# Step_Motor_Driver.net
KiCad netlist of a schematic drawn in Altium Designer
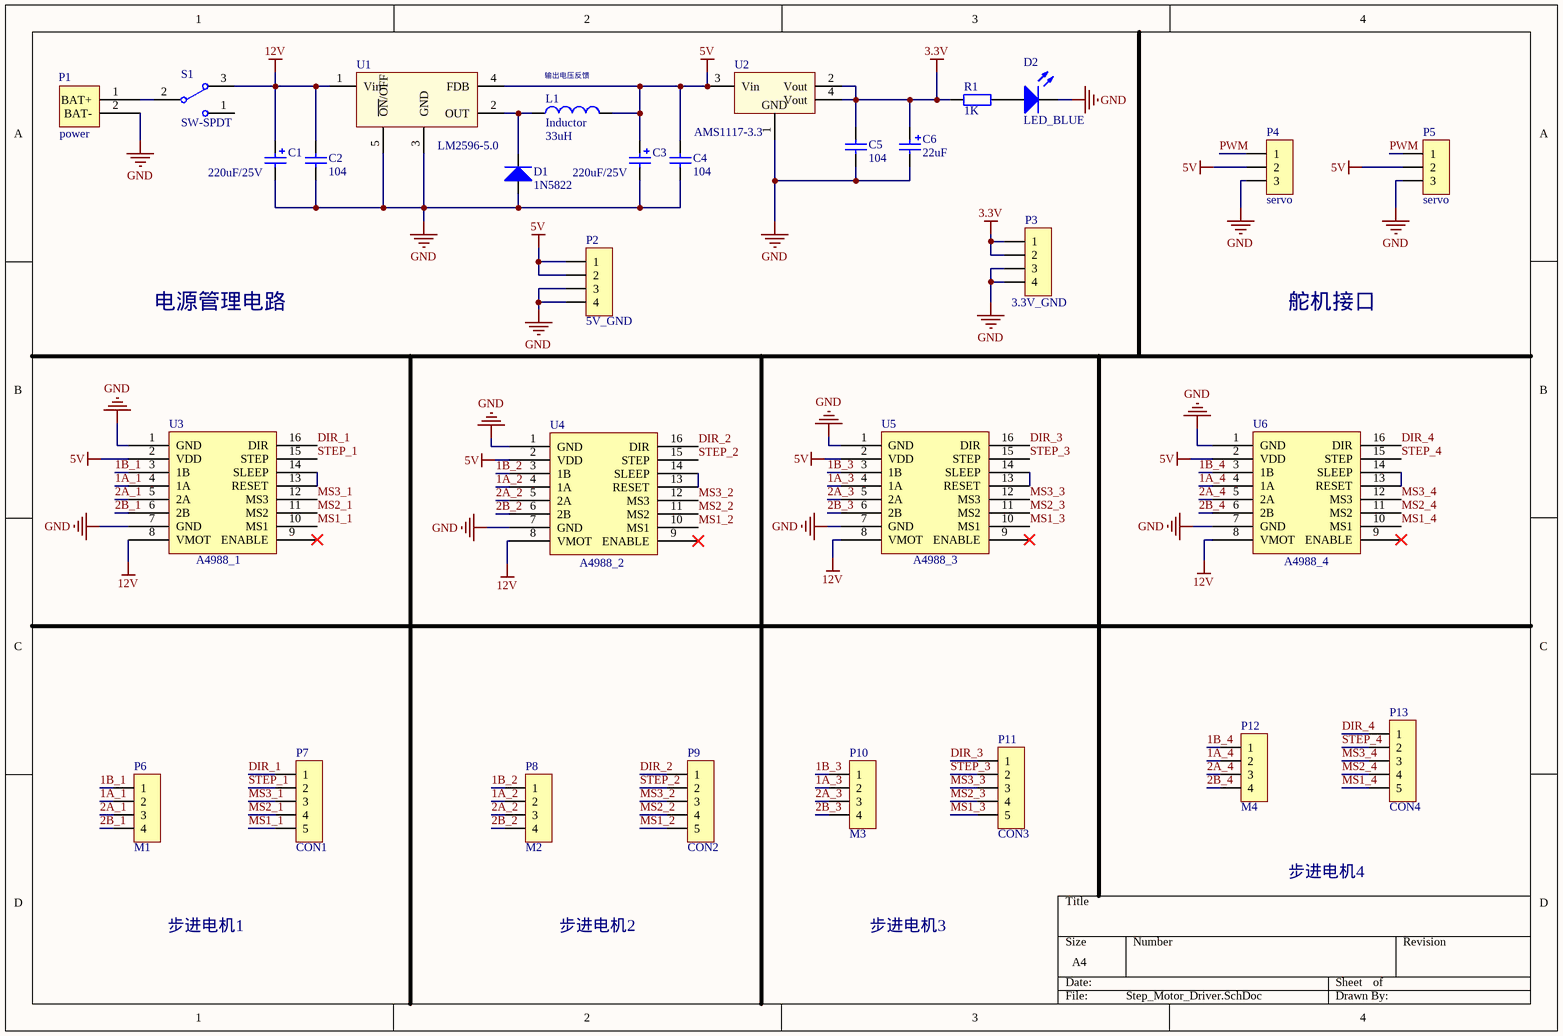
[diagram p0: Step_Motor_Driver.SchDoc]

(export (version "E")
  (design (tool "Eeschema 10.0.6"))
  (components
    (comp (ref "C1")
      (value "220uF/25V")
      (footprint "CAP POL [25V]")
      (description "220uF/35V")
      (libsource (lib "Step_Motor_Driver") (part "Cap Pol [220uF/35V]"))
    )
    (comp (ref "C2")
      (value "Cap")
      (footprint "0805C")
      (fields (field (name "ALTIUM_UNNAMED_1") "104"))
      (libsource (lib "Step_Motor_Driver") (part "Cap_1"))
    )
    (comp (ref "C3")
      (value "220uF/25V")
      (footprint "CAP POL [25V]")
      (description "220uF/35V")
      (libsource (lib "Step_Motor_Driver") (part "Cap Pol [220uF/35V]"))
    )
    (comp (ref "C4")
      (value "Cap")
      (footprint "0805C")
      (fields (field (name "ALTIUM_UNNAMED_1") "104"))
      (libsource (lib "Step_Motor_Driver") (part "Cap_1"))
    )
    (comp (ref "C5")
      (value "Cap")
      (footprint "0805C")
      (fields (field (name "ALTIUM_UNNAMED_1") "104"))
      (libsource (lib "Step_Motor_Driver") (part "Cap_1"))
    )
    (comp (ref "C6")
      (value "Cap Pol(22uF)")
      (footprint "CAP[1210]")
      (fields (field (name "ALTIUM_UNNAMED_1") "22uF"))
      (libsource (lib "Step_Motor_Driver") (part "Cap Pol(22uF)"))
    )
    (comp (ref "D1")
      (value "1N5822")
      (footprint "SS34_3D")
      (description "二极管")
      (libsource (lib "Step_Motor_Driver") (part "1N5819_1"))
    )
    (comp (ref "D2")
      (value "LED_BLUE")
      (footprint "0805LED1")
      (libsource (lib "Step_Motor_Driver") (part "LED_BLUE"))
    )
    (comp (ref "L1")
      (value "Inductor")
      (footprint "Inductor_T10uH")
      (fields (field (name "ALTIUM_UNNAMED_1") "33uH"))
      (libsource (lib "Step_Motor_Driver") (part "Inductor_1"))
    )
    (comp (ref "P1")
      (value "power")
      (footprint "电源端子")
      (description "电源输入")
      (libsource (lib "Step_Motor_Driver") (part "POWER"))
    )
    (comp (ref "P2")
      (value "5V_GND")
      (footprint "HDR2.54-LI-4P")
      (description "4P接插件")
      (fields (field (name "版权归属") "源创客"))
      (libsource (lib "Step_Motor_Driver") (part "Header 4"))
    )
    (comp (ref "P3")
      (value "3.3V_GND")
      (footprint "HDR2.54-LI-4P")
      (description "4P接插件")
      (fields (field (name "版权归属") "源创客"))
      (libsource (lib "Step_Motor_Driver") (part "Header 4"))
    )
    (comp (ref "P4")
      (value "servo")
      (footprint "HDR2.54-LI-3P")
      (description "3P接插件")
      (fields (field (name "版权归属") "源创客"))
      (libsource (lib "Step_Motor_Driver") (part "Header 3"))
    )
    (comp (ref "P5")
      (value "servo")
      (footprint "HDR2.54-LI-3P")
      (description "3P接插件")
      (fields (field (name "版权归属") "源创客"))
      (libsource (lib "Step_Motor_Driver") (part "Header 3"))
    )
    (comp (ref "P6")
      (value "M1")
      (footprint "HDR2.54-LI-4P")
      (description "4P接插件")
      (fields (field (name "版权归属") "源创客"))
      (libsource (lib "Step_Motor_Driver") (part "Header 4"))
    )
    (comp (ref "P7")
      (value "CON1")
      (footprint "HDR2.54-LI-5P")
      (description "5P接插件")
      (fields (field (name "版权归属") "源创客"))
      (libsource (lib "Step_Motor_Driver") (part "Header 5"))
    )
    (comp (ref "P8")
      (value "M2")
      (footprint "HDR2.54-LI-4P")
      (description "4P接插件")
      (fields (field (name "版权归属") "源创客"))
      (libsource (lib "Step_Motor_Driver") (part "Header 4"))
    )
    (comp (ref "P9")
      (value "CON2")
      (footprint "HDR2.54-LI-5P")
      (description "5P接插件")
      (fields (field (name "版权归属") "源创客"))
      (libsource (lib "Step_Motor_Driver") (part "Header 5"))
    )
    (comp (ref "P10")
      (value "M3")
      (footprint "HDR2.54-LI-4P")
      (description "4P接插件")
      (fields (field (name "版权归属") "源创客"))
      (libsource (lib "Step_Motor_Driver") (part "Header 4"))
    )
    (comp (ref "P11")
      (value "CON3")
      (footprint "HDR2.54-LI-5P")
      (description "5P接插件")
      (fields (field (name "版权归属") "源创客"))
      (libsource (lib "Step_Motor_Driver") (part "Header 5"))
    )
    (comp (ref "P12")
      (value "M4")
      (footprint "HDR2.54-LI-4P")
      (description "4P接插件")
      (fields (field (name "版权归属") "源创客"))
      (libsource (lib "Step_Motor_Driver") (part "Header 4"))
    )
    (comp (ref "P13")
      (value "CON4")
      (footprint "HDR2.54-LI-5P")
      (description "5P接插件")
      (fields (field (name "版权归属") "源创客"))
      (libsource (lib "Step_Motor_Driver") (part "Header 5"))
    )
    (comp (ref "R1")
      (value "Res2")
      (footprint "0805R")
      (fields (field (name "ALTIUM_UNNAMED_1") "1K"))
      (libsource (lib "Step_Motor_Driver") (part "Res2"))
    )
    (comp (ref "S1")
      (value "SW-SPDT")
      (footprint "SW-TO3")
      (description "SPDT Subminiature Toggle Switch, Right Angle Mounting, Vertical Actuation")
      (fields (field (name "PUBLISHER") "Altium Limited"))
      (libsource (lib "Step_Motor_Driver") (part "SW-SPDT"))
    )
    (comp (ref "U1")
      (value "LM2596-5.0")
      (footprint "TO-263-5")
      (description "IC")
      (libsource (lib "Step_Motor_Driver") (part "LM2596-5.0"))
    )
    (comp (ref "U2")
      (value "AMS1117-3.3")
      (footprint "SOT-223")
      (libsource (lib "Step_Motor_Driver") (part "AMS1117-3.3"))
    )
    (comp (ref "U3")
      (value "A4988_1")
      (footprint "A4988")
      (description "A4988 Module")
      (libsource (lib "Step_Motor_Driver") (part "A4988"))
    )
    (comp (ref "U4")
      (value "A4988_2")
      (footprint "A4988")
      (description "A4988 Module")
      (libsource (lib "Step_Motor_Driver") (part "A4988"))
    )
    (comp (ref "U5")
      (value "A4988_3")
      (footprint "A4988")
      (description "A4988 Module")
      (libsource (lib "Step_Motor_Driver") (part "A4988"))
    )
    (comp (ref "U6")
      (value "A4988_4")
      (footprint "A4988")
      (description "A4988 Module")
      (libsource (lib "Step_Motor_Driver") (part "A4988"))
    )
  )
  (nets
    (net (code "1") (name "/1A_1") (class "Default")
      (node (ref "P6") (pin "2") (pinfunction "2_2") (pintype "passive"))
      (node (ref "U3") (pin "4") (pinfunction "1A_4") (pintype "passive"))
    )
    (net (code "2") (name "/1A_2") (class "Default")
      (node (ref "P8") (pin "2") (pinfunction "2_2") (pintype "passive"))
      (node (ref "U4") (pin "4") (pinfunction "1A_4") (pintype "passive"))
    )
    (net (code "3") (name "/1A_3") (class "Default")
      (node (ref "P10") (pin "2") (pinfunction "2_2") (pintype "passive"))
      (node (ref "U5") (pin "4") (pinfunction "1A_4") (pintype "passive"))
    )
    (net (code "4") (name "/1A_4") (class "Default")
      (node (ref "P12") (pin "2") (pinfunction "2_2") (pintype "passive"))
      (node (ref "U6") (pin "4") (pinfunction "1A_4") (pintype "passive"))
    )
    (net (code "5") (name "/1B_1") (class "Default")
      (node (ref "P6") (pin "1") (pinfunction "1_1") (pintype "passive"))
      (node (ref "U3") (pin "3") (pinfunction "1B_3") (pintype "passive"))
    )
    (net (code "6") (name "/1B_2") (class "Default")
      (node (ref "P8") (pin "1") (pinfunction "1_1") (pintype "passive"))
      (node (ref "U4") (pin "3") (pinfunction "1B_3") (pintype "passive"))
    )
    (net (code "7") (name "/1B_3") (class "Default")
      (node (ref "P10") (pin "1") (pinfunction "1_1") (pintype "passive"))
      (node (ref "U5") (pin "3") (pinfunction "1B_3") (pintype "passive"))
    )
    (net (code "8") (name "/1B_4") (class "Default")
      (node (ref "P12") (pin "1") (pinfunction "1_1") (pintype "passive"))
      (node (ref "U6") (pin "3") (pinfunction "1B_3") (pintype "passive"))
    )
    (net (code "9") (name "/2A_1") (class "Default")
      (node (ref "P6") (pin "3") (pinfunction "3_3") (pintype "passive"))
      (node (ref "U3") (pin "5") (pinfunction "2A_5") (pintype "passive"))
    )
    (net (code "10") (name "/2A_2") (class "Default")
      (node (ref "P8") (pin "3") (pinfunction "3_3") (pintype "passive"))
      (node (ref "U4") (pin "5") (pinfunction "2A_5") (pintype "passive"))
    )
    (net (code "11") (name "/2A_3") (class "Default")
      (node (ref "P10") (pin "3") (pinfunction "3_3") (pintype "passive"))
      (node (ref "U5") (pin "5") (pinfunction "2A_5") (pintype "passive"))
    )
    (net (code "12") (name "/2A_4") (class "Default")
      (node (ref "P12") (pin "3") (pinfunction "3_3") (pintype "passive"))
      (node (ref "U6") (pin "5") (pinfunction "2A_5") (pintype "passive"))
    )
    (net (code "13") (name "/2B_1") (class "Default")
      (node (ref "P6") (pin "4") (pinfunction "4_4") (pintype "passive"))
      (node (ref "U3") (pin "6") (pinfunction "2B_6") (pintype "passive"))
    )
    (net (code "14") (name "/2B_2") (class "Default")
      (node (ref "P8") (pin "4") (pinfunction "4_4") (pintype "passive"))
      (node (ref "U4") (pin "6") (pinfunction "2B_6") (pintype "passive"))
    )
    (net (code "15") (name "/2B_3") (class "Default")
      (node (ref "P10") (pin "4") (pinfunction "4_4") (pintype "passive"))
      (node (ref "U5") (pin "6") (pinfunction "2B_6") (pintype "passive"))
    )
    (net (code "16") (name "/2B_4") (class "Default")
      (node (ref "P12") (pin "4") (pinfunction "4_4") (pintype "passive"))
      (node (ref "U6") (pin "6") (pinfunction "2B_6") (pintype "passive"))
    )
    (net (code "17") (name "/DIR_1") (class "Default")
      (node (ref "P7") (pin "1") (pinfunction "1_1") (pintype "passive"))
      (node (ref "U3") (pin "16") (pinfunction "DIR_16") (pintype "passive"))
    )
    (net (code "18") (name "/DIR_2") (class "Default")
      (node (ref "P9") (pin "1") (pinfunction "1_1") (pintype "passive"))
      (node (ref "U4") (pin "16") (pinfunction "DIR_16") (pintype "passive"))
    )
    (net (code "19") (name "/DIR_3") (class "Default")
      (node (ref "P11") (pin "1") (pinfunction "1_1") (pintype "passive"))
      (node (ref "U5") (pin "16") (pinfunction "DIR_16") (pintype "passive"))
    )
    (net (code "20") (name "/DIR_4") (class "Default")
      (node (ref "P13") (pin "1") (pinfunction "1_1") (pintype "passive"))
      (node (ref "U6") (pin "16") (pinfunction "DIR_16") (pintype "passive"))
    )
    (net (code "21") (name "/MS1_1") (class "Default")
      (node (ref "P7") (pin "5") (pinfunction "5_5") (pintype "passive"))
      (node (ref "U3") (pin "10") (pinfunction "MS1_10") (pintype "passive"))
    )
    (net (code "22") (name "/MS1_2") (class "Default")
      (node (ref "P9") (pin "5") (pinfunction "5_5") (pintype "passive"))
      (node (ref "U4") (pin "10") (pinfunction "MS1_10") (pintype "passive"))
    )
    (net (code "23") (name "/MS1_3") (class "Default")
      (node (ref "P11") (pin "5") (pinfunction "5_5") (pintype "passive"))
      (node (ref "U5") (pin "10") (pinfunction "MS1_10") (pintype "passive"))
    )
    (net (code "24") (name "/MS1_4") (class "Default")
      (node (ref "P13") (pin "5") (pinfunction "5_5") (pintype "passive"))
      (node (ref "U6") (pin "10") (pinfunction "MS1_10") (pintype "passive"))
    )
    (net (code "25") (name "/MS2_1") (class "Default")
      (node (ref "P7") (pin "4") (pinfunction "4_4") (pintype "passive"))
      (node (ref "U3") (pin "11") (pinfunction "MS2_11") (pintype "passive"))
    )
    (net (code "26") (name "/MS2_2") (class "Default")
      (node (ref "P9") (pin "4") (pinfunction "4_4") (pintype "passive"))
      (node (ref "U4") (pin "11") (pinfunction "MS2_11") (pintype "passive"))
    )
    (net (code "27") (name "/MS2_3") (class "Default")
      (node (ref "P11") (pin "4") (pinfunction "4_4") (pintype "passive"))
      (node (ref "U5") (pin "11") (pinfunction "MS2_11") (pintype "passive"))
    )
    (net (code "28") (name "/MS2_4") (class "Default")
      (node (ref "P13") (pin "4") (pinfunction "4_4") (pintype "passive"))
      (node (ref "U6") (pin "11") (pinfunction "MS2_11") (pintype "passive"))
    )
    (net (code "29") (name "/MS3_1") (class "Default")
      (node (ref "P7") (pin "3") (pinfunction "3_3") (pintype "passive"))
      (node (ref "U3") (pin "12") (pinfunction "MS3_12") (pintype "passive"))
    )
    (net (code "30") (name "/MS3_2") (class "Default")
      (node (ref "P9") (pin "3") (pinfunction "3_3") (pintype "passive"))
      (node (ref "U4") (pin "12") (pinfunction "MS3_12") (pintype "passive"))
    )
    (net (code "31") (name "/MS3_3") (class "Default")
      (node (ref "P11") (pin "3") (pinfunction "3_3") (pintype "passive"))
      (node (ref "U5") (pin "12") (pinfunction "MS3_12") (pintype "passive"))
    )
    (net (code "32") (name "/MS3_4") (class "Default")
      (node (ref "P13") (pin "3") (pinfunction "3_3") (pintype "passive"))
      (node (ref "U6") (pin "12") (pinfunction "MS3_12") (pintype "passive"))
    )
    (net (code "33") (name "/PWM") (class "Default")
      (node (ref "P4") (pin "1") (pinfunction "1_1") (pintype "passive"))
      (node (ref "P5") (pin "1") (pinfunction "1_1") (pintype "passive"))
    )
    (net (code "34") (name "/STEP_1") (class "Default")
      (node (ref "P7") (pin "2") (pinfunction "2_2") (pintype "passive"))
      (node (ref "U3") (pin "15") (pinfunction "STEP_15") (pintype "passive"))
    )
    (net (code "35") (name "/STEP_2") (class "Default")
      (node (ref "P9") (pin "2") (pinfunction "2_2") (pintype "passive"))
      (node (ref "U4") (pin "15") (pinfunction "STEP_15") (pintype "passive"))
    )
    (net (code "36") (name "/STEP_3") (class "Default")
      (node (ref "P11") (pin "2") (pinfunction "2_2") (pintype "passive"))
      (node (ref "U5") (pin "15") (pinfunction "STEP_15") (pintype "passive"))
    )
    (net (code "37") (name "/STEP_4") (class "Default")
      (node (ref "P13") (pin "2") (pinfunction "2_2") (pintype "passive"))
      (node (ref "U6") (pin "15") (pinfunction "STEP_15") (pintype "passive"))
    )
    (net (code "38") (name "3.3V") (class "Default")
      (node (ref "C5") (pin "2") (pinfunction "2_2") (pintype "passive"))
      (node (ref "C6") (pin "1") (pinfunction "1_1") (pintype "passive"))
      (node (ref "P3") (pin "1") (pinfunction "1_1") (pintype "passive"))
      (node (ref "P3") (pin "2") (pinfunction "2_2") (pintype "passive"))
      (node (ref "R1") (pin "1") (pinfunction "1_1") (pintype "passive"))
      (node (ref "U2") (pin "2") (pinfunction "Vout_2") (pintype "passive"))
      (node (ref "U2") (pin "4") (pinfunction "Vout_4") (pintype "passive"))
    )
    (net (code "39") (name "5V") (class "Default")
      (node (ref "C3") (pin "1") (pinfunction "1_1") (pintype "passive"))
      (node (ref "C4") (pin "1") (pinfunction "1_1") (pintype "passive"))
      (node (ref "L1") (pin "2") (pinfunction "2_2") (pintype "passive"))
      (node (ref "P2") (pin "1") (pinfunction "1_1") (pintype "passive"))
      (node (ref "P2") (pin "2") (pinfunction "2_2") (pintype "passive"))
      (node (ref "P4") (pin "2") (pinfunction "2_2") (pintype "passive"))
      (node (ref "P5") (pin "2") (pinfunction "2_2") (pintype "passive"))
      (node (ref "U1") (pin "4") (pinfunction "FDB_4") (pintype "passive"))
      (node (ref "U2") (pin "3") (pinfunction "Vin_3") (pintype "passive"))
      (node (ref "U3") (pin "2") (pinfunction "VDD_2") (pintype "passive"))
      (node (ref "U4") (pin "2") (pinfunction "VDD_2") (pintype "passive"))
      (node (ref "U5") (pin "2") (pinfunction "VDD_2") (pintype "passive"))
      (node (ref "U6") (pin "2") (pinfunction "VDD_2") (pintype "passive"))
    )
    (net (code "40") (name "12V") (class "Default")
      (node (ref "C1") (pin "1") (pinfunction "1_1") (pintype "passive"))
      (node (ref "C2") (pin "1") (pinfunction "1_1") (pintype "passive"))
      (node (ref "S1") (pin "3") (pinfunction "3_3") (pintype "passive"))
      (node (ref "U1") (pin "1") (pinfunction "Vin_1") (pintype "passive"))
      (node (ref "U3") (pin "8") (pinfunction "VMOT_8") (pintype "passive"))
      (node (ref "U4") (pin "8") (pinfunction "VMOT_8") (pintype "passive"))
      (node (ref "U5") (pin "8") (pinfunction "VMOT_8") (pintype "passive"))
      (node (ref "U6") (pin "8") (pinfunction "VMOT_8") (pintype "passive"))
    )
    (net (code "41") (name "GND") (class "Default")
      (node (ref "C1") (pin "2") (pinfunction "2_2") (pintype "passive"))
      (node (ref "C2") (pin "2") (pinfunction "2_2") (pintype "passive"))
      (node (ref "C3") (pin "2") (pinfunction "2_2") (pintype "passive"))
      (node (ref "C4") (pin "2") (pinfunction "2_2") (pintype "passive"))
      (node (ref "C5") (pin "1") (pinfunction "1_1") (pintype "passive"))
      (node (ref "C6") (pin "2") (pinfunction "2_2") (pintype "passive"))
      (node (ref "D1") (pin "1") (pinfunction "1_1") (pintype "passive"))
      (node (ref "D2") (pin "2") (pinfunction "K_2") (pintype "passive"))
      (node (ref "P1") (pin "2") (pinfunction "BAT-_2") (pintype "passive"))
      (node (ref "P2") (pin "3") (pinfunction "3_3") (pintype "passive"))
      (node (ref "P2") (pin "4") (pinfunction "4_4") (pintype "passive"))
      (node (ref "P3") (pin "3") (pinfunction "3_3") (pintype "passive"))
      (node (ref "P3") (pin "4") (pinfunction "4_4") (pintype "passive"))
      (node (ref "P4") (pin "3") (pinfunction "3_3") (pintype "passive"))
      (node (ref "P5") (pin "3") (pinfunction "3_3") (pintype "passive"))
      (node (ref "U1") (pin "3") (pinfunction "GND_3") (pintype "passive"))
      (node (ref "U1") (pin "5") (pinfunction "~{ON}/OFF_5") (pintype "passive"))
      (node (ref "U2") (pin "1") (pinfunction "GND_1") (pintype "passive"))
      (node (ref "U3") (pin "1") (pinfunction "GND_1") (pintype "passive"))
      (node (ref "U3") (pin "7") (pinfunction "GND_7") (pintype "passive"))
      (node (ref "U4") (pin "1") (pinfunction "GND_1") (pintype "passive"))
      (node (ref "U4") (pin "7") (pinfunction "GND_7") (pintype "passive"))
      (node (ref "U5") (pin "1") (pinfunction "GND_1") (pintype "passive"))
      (node (ref "U5") (pin "7") (pinfunction "GND_7") (pintype "passive"))
      (node (ref "U6") (pin "1") (pinfunction "GND_1") (pintype "passive"))
      (node (ref "U6") (pin "7") (pinfunction "GND_7") (pintype "passive"))
    )
    (net (code "42") (name "Net-(D2-A)") (class "Default")
      (node (ref "D2") (pin "1") (pinfunction "A_1") (pintype "passive"))
      (node (ref "R1") (pin "2") (pinfunction "2_2") (pintype "passive"))
    )
    (net (code "43") (name "Net-(P1-BAT+)") (class "Default")
      (node (ref "P1") (pin "1") (pinfunction "BAT+_1") (pintype "passive"))
      (node (ref "S1") (pin "2") (pinfunction "2_2") (pintype "passive"))
    )
    (net (code "44") (name "Net-(U1-OUT)") (class "Default")
      (node (ref "D1") (pin "2") (pinfunction "2_2") (pintype "passive"))
      (node (ref "L1") (pin "1") (pinfunction "1_1") (pintype "passive"))
      (node (ref "U1") (pin "2") (pinfunction "OUT_2") (pintype "passive"))
    )
    (net (code "45") (name "Net-(U3-RESET)") (class "Default")
      (node (ref "U3") (pin "13") (pinfunction "RESET_13") (pintype "passive"))
      (node (ref "U3") (pin "14") (pinfunction "SLEEP_14") (pintype "passive"))
    )
    (net (code "46") (name "Net-(U4-RESET)") (class "Default")
      (node (ref "U4") (pin "13") (pinfunction "RESET_13") (pintype "passive"))
      (node (ref "U4") (pin "14") (pinfunction "SLEEP_14") (pintype "passive"))
    )
    (net (code "47") (name "Net-(U5-RESET)") (class "Default")
      (node (ref "U5") (pin "13") (pinfunction "RESET_13") (pintype "passive"))
      (node (ref "U5") (pin "14") (pinfunction "SLEEP_14") (pintype "passive"))
    )
    (net (code "48") (name "Net-(U6-RESET)") (class "Default")
      (node (ref "U6") (pin "13") (pinfunction "RESET_13") (pintype "passive"))
      (node (ref "U6") (pin "14") (pinfunction "SLEEP_14") (pintype "passive"))
    )
    (net (code "49") (name "unconnected-(S1-Pad1)") (class "Default")
      (node (ref "S1") (pin "1") (pinfunction "1_1") (pintype "passive"))
    )
    (net (code "50") (name "unconnected-(U3-ENABLE-Pad9)") (class "Default")
      (node (ref "U3") (pin "9") (pinfunction "ENABLE_9") (pintype "passive+no_connect"))
    )
    (net (code "51") (name "unconnected-(U4-ENABLE-Pad9)") (class "Default")
      (node (ref "U4") (pin "9") (pinfunction "ENABLE_9") (pintype "passive+no_connect"))
    )
    (net (code "52") (name "unconnected-(U5-ENABLE-Pad9)") (class "Default")
      (node (ref "U5") (pin "9") (pinfunction "ENABLE_9") (pintype "passive+no_connect"))
    )
    (net (code "53") (name "unconnected-(U6-ENABLE-Pad9)") (class "Default")
      (node (ref "U6") (pin "9") (pinfunction "ENABLE_9") (pintype "passive+no_connect"))
    )
  )
)
